# atmega_multimedia_control.net
KiCad netlist of a schematic drawn in EAGLE
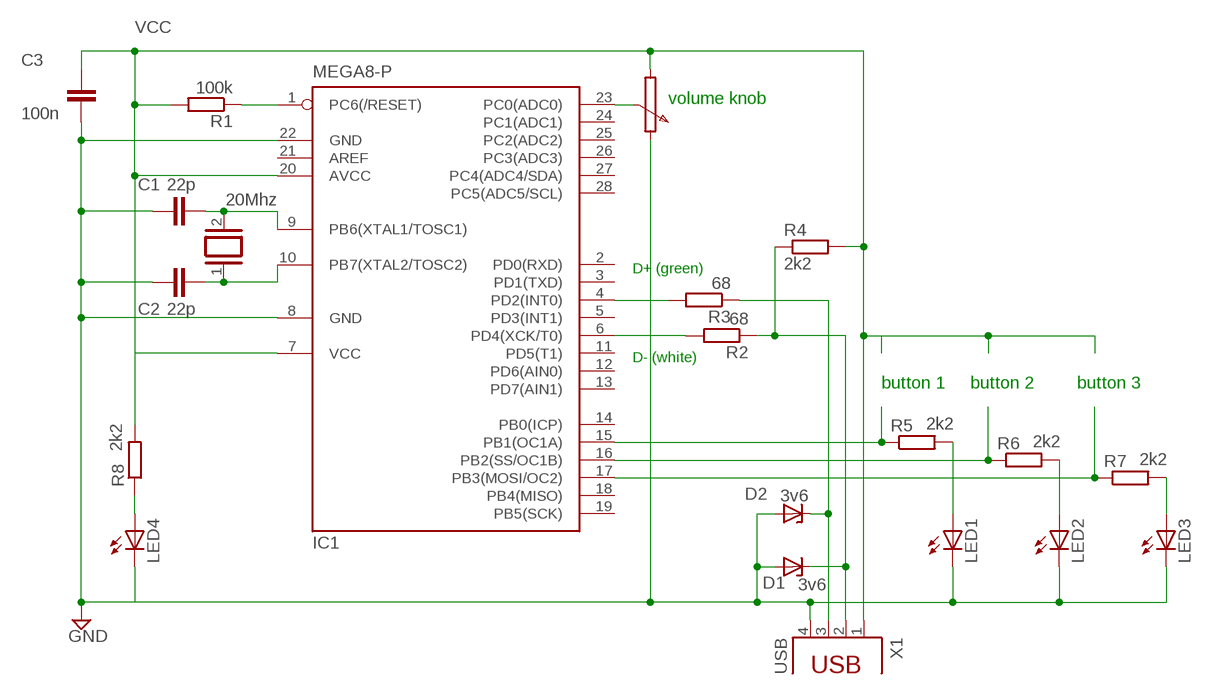
[diagram p0: schematic, sheet 1]

(export (version "E")
  (design (tool "Eeschema 10.0.6"))
  (components
    (comp (ref "C1")
      (value "22p")
      (footprint "eagle-import:C025-025X050")
      (libsource (lib "eagle-import") (part "C-EU025-025X050"))
    )
    (comp (ref "C2")
      (value "22p")
      (footprint "eagle-import:C025-025X050")
      (libsource (lib "eagle-import") (part "C-EU025-025X050"))
    )
    (comp (ref "C3")
      (value "100n")
      (footprint "eagle-import:C025-025X050")
      (libsource (lib "eagle-import") (part "C-EU025-025X050"))
    )
    (comp (ref "D1")
      (value "3v6")
      (footprint "eagle-import:DO34Z7")
      (libsource (lib "eagle-import") (part "ZENER-DIODEDO34-7"))
    )
    (comp (ref "D2")
      (value "3v6")
      (footprint "eagle-import:DO34Z7")
      (libsource (lib "eagle-import") (part "ZENER-DIODEDO34-7"))
    )
    (comp (ref "IC1")
      (value "MEGA8-P")
      (footprint "eagle-import:DIL28-3")
      (libsource (lib "eagle-import") (part "MEGA8-P"))
    )
    (comp (ref "LED1")
      (value "LED3MM")
      (footprint "eagle-import:LED3MM")
      (libsource (lib "eagle-import") (part "LED3MM"))
    )
    (comp (ref "LED2")
      (value "LED3MM")
      (footprint "eagle-import:LED3MM")
      (libsource (lib "eagle-import") (part "LED3MM"))
    )
    (comp (ref "LED3")
      (value "LED3MM")
      (footprint "eagle-import:LED3MM")
      (libsource (lib "eagle-import") (part "LED3MM"))
    )
    (comp (ref "LED4")
      (value "LED3MM")
      (footprint "eagle-import:LED3MM")
      (libsource (lib "eagle-import") (part "LED3MM"))
    )
    (comp (ref "Q1")
      (value "20Mhz")
      (footprint "eagle-import:QS")
      (libsource (lib "eagle-import") (part "XTAL/S"))
    )
    (comp (ref "R1")
      (value "100k")
      (footprint "eagle-import:0204_7")
      (libsource (lib "eagle-import") (part "R-EU_0204/7"))
    )
    (comp (ref "R2")
      (value "68")
      (footprint "eagle-import:0204_7")
      (libsource (lib "eagle-import") (part "R-EU_0204/7"))
    )
    (comp (ref "R3")
      (value "68")
      (footprint "eagle-import:0204_7")
      (libsource (lib "eagle-import") (part "R-EU_0204/7"))
    )
    (comp (ref "R4")
      (value "2k2")
      (footprint "eagle-import:0204_7")
      (libsource (lib "eagle-import") (part "R-EU_0204/7"))
    )
    (comp (ref "R5")
      (value "2k2")
      (footprint "eagle-import:0204_7")
      (libsource (lib "eagle-import") (part "R-EU_0204/7"))
    )
    (comp (ref "R6")
      (value "2k2")
      (footprint "eagle-import:0204_7")
      (libsource (lib "eagle-import") (part "R-EU_0204/7"))
    )
    (comp (ref "R7")
      (value "2k2")
      (footprint "eagle-import:0204_7")
      (libsource (lib "eagle-import") (part "R-EU_0204/7"))
    )
    (comp (ref "R8")
      (value "2k2")
      (footprint "eagle-import:0204_7")
      (libsource (lib "eagle-import") (part "R-EU_0204/7"))
    )
    (comp (ref "X1")
      (value "USB")
      (footprint "eagle-import:PN61729")
      (libsource (lib "eagle-import") (part "PN61729"))
    )
  )
  (nets
    (net (code "1") (name "/VCC") (class "Default")
      (node (ref "C3") (pin "2") (pinfunction "2_2") (pintype "passive"))
      (node (ref "IC1") (pin "20") (pinfunction "AVCC_20") (pintype "power_in"))
      (node (ref "IC1") (pin "7") (pinfunction "VCC_7") (pintype "power_in"))
      (node (ref "R1") (pin "2") (pinfunction "2_2") (pintype "passive"))
      (node (ref "R4") (pin "2") (pinfunction "2_2") (pintype "passive"))
      (node (ref "R8") (pin "2") (pinfunction "2_2") (pintype "passive"))
      (node (ref "X1") (pin "1") (pinfunction "1_1") (pintype "passive"))
    )
    (net (code "2") (name "GND") (class "Default")
      (node (ref "C1") (pin "1") (pinfunction "1_1") (pintype "passive"))
      (node (ref "C2") (pin "1") (pinfunction "1_1") (pintype "passive"))
      (node (ref "C3") (pin "1") (pinfunction "1_1") (pintype "passive"))
      (node (ref "D1") (pin "A") (pinfunction "A_A") (pintype "passive"))
      (node (ref "D2") (pin "A") (pinfunction "A_A") (pintype "passive"))
      (node (ref "IC1") (pin "22") (pinfunction "GND_22") (pintype "power_in"))
      (node (ref "IC1") (pin "8") (pinfunction "GND_8") (pintype "power_in"))
      (node (ref "LED1") (pin "K") (pinfunction "C_K") (pintype "passive"))
      (node (ref "LED2") (pin "K") (pinfunction "C_K") (pintype "passive"))
      (node (ref "LED3") (pin "K") (pinfunction "C_K") (pintype "passive"))
      (node (ref "LED4") (pin "K") (pinfunction "C_K") (pintype "passive"))
      (node (ref "X1") (pin "4") (pinfunction "4_4") (pintype "passive"))
    )
    (net (code "3") (name "Net-(D1-PadC)") (class "Default")
      (node (ref "D1") (pin "C") (pinfunction "C_C") (pintype "passive"))
      (node (ref "R2") (pin "1") (pinfunction "1_1") (pintype "passive"))
      (node (ref "R4") (pin "1") (pinfunction "1_1") (pintype "passive"))
      (node (ref "X1") (pin "2") (pinfunction "2_2") (pintype "passive"))
    )
    (net (code "4") (name "Net-(D2-PadC)") (class "Default")
      (node (ref "D2") (pin "C") (pinfunction "C_C") (pintype "passive"))
      (node (ref "R3") (pin "1") (pinfunction "1_1") (pintype "passive"))
      (node (ref "X1") (pin "3") (pinfunction "3_3") (pintype "passive"))
    )
    (net (code "5") (name "Net-(IC1-PB1(OC1A))") (class "Default")
      (node (ref "IC1") (pin "15") (pinfunction "PB1(OC1A)_15") (pintype "bidirectional"))
      (node (ref "R5") (pin "1") (pinfunction "1_1") (pintype "passive"))
    )
    (net (code "6") (name "Net-(IC1-PB2(SS{slash}OC1B))") (class "Default")
      (node (ref "IC1") (pin "16") (pinfunction "PB2(SS/OC1B)_16") (pintype "bidirectional"))
      (node (ref "R6") (pin "1") (pinfunction "1_1") (pintype "passive"))
    )
    (net (code "7") (name "Net-(IC1-PB3(MOSI{slash}OC2))") (class "Default")
      (node (ref "IC1") (pin "17") (pinfunction "PB3(MOSI/OC2)_17") (pintype "bidirectional"))
      (node (ref "R7") (pin "1") (pinfunction "1_1") (pintype "passive"))
    )
    (net (code "8") (name "Net-(IC1-PB6(XTAL1{slash}TOSC1))") (class "Default")
      (node (ref "C1") (pin "2") (pinfunction "2_2") (pintype "passive"))
      (node (ref "IC1") (pin "9") (pinfunction "PB6(XTAL1/TOSC1)_9") (pintype "bidirectional"))
      (node (ref "Q1") (pin "2") (pinfunction "2_2") (pintype "passive"))
    )
    (net (code "9") (name "Net-(IC1-PB7(XTAL2{slash}TOSC2))") (class "Default")
      (node (ref "C2") (pin "2") (pinfunction "2_2") (pintype "passive"))
      (node (ref "IC1") (pin "10") (pinfunction "PB7(XTAL2/TOSC2)_10") (pintype "bidirectional"))
      (node (ref "Q1") (pin "1") (pinfunction "1_1") (pintype "passive"))
    )
    (net (code "10") (name "Net-(IC1-PC6({slash}RESET))") (class "Default")
      (node (ref "IC1") (pin "1") (pinfunction "PC6(/RESET)_1") (pintype "bidirectional"))
      (node (ref "R1") (pin "1") (pinfunction "1_1") (pintype "passive"))
    )
    (net (code "11") (name "Net-(IC1-PD2(INT0))") (class "Default")
      (node (ref "IC1") (pin "4") (pinfunction "PD2(INT0)_4") (pintype "bidirectional"))
      (node (ref "R3") (pin "2") (pinfunction "2_2") (pintype "passive"))
    )
    (net (code "12") (name "Net-(IC1-PD4(XCK{slash}T0))") (class "Default")
      (node (ref "IC1") (pin "6") (pinfunction "PD4(XCK/T0)_6") (pintype "bidirectional"))
      (node (ref "R2") (pin "2") (pinfunction "2_2") (pintype "passive"))
    )
    (net (code "13") (name "Net-(LED1-PadA)") (class "Default")
      (node (ref "LED1") (pin "A") (pinfunction "A_A") (pintype "passive"))
      (node (ref "R5") (pin "2") (pinfunction "2_2") (pintype "passive"))
    )
    (net (code "14") (name "Net-(LED2-PadA)") (class "Default")
      (node (ref "LED2") (pin "A") (pinfunction "A_A") (pintype "passive"))
      (node (ref "R6") (pin "2") (pinfunction "2_2") (pintype "passive"))
    )
    (net (code "15") (name "Net-(LED3-PadA)") (class "Default")
      (node (ref "LED3") (pin "A") (pinfunction "A_A") (pintype "passive"))
      (node (ref "R7") (pin "2") (pinfunction "2_2") (pintype "passive"))
    )
    (net (code "16") (name "Net-(LED4-PadA)") (class "Default")
      (node (ref "LED4") (pin "A") (pinfunction "A_A") (pintype "passive"))
      (node (ref "R8") (pin "1") (pinfunction "1_1") (pintype "passive"))
    )
    (net (code "17") (name "unconnected-(IC1-AREF-Pad21)") (class "Default")
      (node (ref "IC1") (pin "21") (pinfunction "AREF_21") (pintype "passive"))
    )
    (net (code "18") (name "unconnected-(IC1-PB0(ICP)-Pad14)") (class "Default")
      (node (ref "IC1") (pin "14") (pinfunction "PB0(ICP)_14") (pintype "bidirectional"))
    )
    (net (code "19") (name "unconnected-(IC1-PB4(MISO)-Pad18)") (class "Default")
      (node (ref "IC1") (pin "18") (pinfunction "PB4(MISO)_18") (pintype "bidirectional"))
    )
    (net (code "20") (name "unconnected-(IC1-PB5(SCK)-Pad19)") (class "Default")
      (node (ref "IC1") (pin "19") (pinfunction "PB5(SCK)_19") (pintype "bidirectional"))
    )
    (net (code "21") (name "unconnected-(IC1-PC0(ADC0)-Pad23)") (class "Default")
      (node (ref "IC1") (pin "23") (pinfunction "PC0(ADC0)_23") (pintype "bidirectional"))
    )
    (net (code "22") (name "unconnected-(IC1-PC1(ADC1)-Pad24)") (class "Default")
      (node (ref "IC1") (pin "24") (pinfunction "PC1(ADC1)_24") (pintype "bidirectional"))
    )
    (net (code "23") (name "unconnected-(IC1-PC2(ADC2)-Pad25)") (class "Default")
      (node (ref "IC1") (pin "25") (pinfunction "PC2(ADC2)_25") (pintype "bidirectional"))
    )
    (net (code "24") (name "unconnected-(IC1-PC3(ADC3)-Pad26)") (class "Default")
      (node (ref "IC1") (pin "26") (pinfunction "PC3(ADC3)_26") (pintype "bidirectional"))
    )
    (net (code "25") (name "unconnected-(IC1-PC4(ADC4{slash}SDA)-Pad27)") (class "Default")
      (node (ref "IC1") (pin "27") (pinfunction "PC4(ADC4/SDA)_27") (pintype "bidirectional"))
    )
    (net (code "26") (name "unconnected-(IC1-PC5(ADC5{slash}SCL)-Pad28)") (class "Default")
      (node (ref "IC1") (pin "28") (pinfunction "PC5(ADC5/SCL)_28") (pintype "bidirectional"))
    )
    (net (code "27") (name "unconnected-(IC1-PD0(RXD)-Pad2)") (class "Default")
      (node (ref "IC1") (pin "2") (pinfunction "PD0(RXD)_2") (pintype "bidirectional"))
    )
    (net (code "28") (name "unconnected-(IC1-PD1(TXD)-Pad3)") (class "Default")
      (node (ref "IC1") (pin "3") (pinfunction "PD1(TXD)_3") (pintype "bidirectional"))
    )
    (net (code "29") (name "unconnected-(IC1-PD3(INT1)-Pad5)") (class "Default")
      (node (ref "IC1") (pin "5") (pinfunction "PD3(INT1)_5") (pintype "bidirectional"))
    )
    (net (code "30") (name "unconnected-(IC1-PD5(T1)-Pad11)") (class "Default")
      (node (ref "IC1") (pin "11") (pinfunction "PD5(T1)_11") (pintype "bidirectional"))
    )
    (net (code "31") (name "unconnected-(IC1-PD6(AIN0)-Pad12)") (class "Default")
      (node (ref "IC1") (pin "12") (pinfunction "PD6(AIN0)_12") (pintype "bidirectional"))
    )
    (net (code "32") (name "unconnected-(IC1-PD7(AIN1)-Pad13)") (class "Default")
      (node (ref "IC1") (pin "13") (pinfunction "PD7(AIN1)_13") (pintype "bidirectional"))
    )
  )
)
